# oled_control.net
KiCad netlist of a schematic drawn in Altium Designer
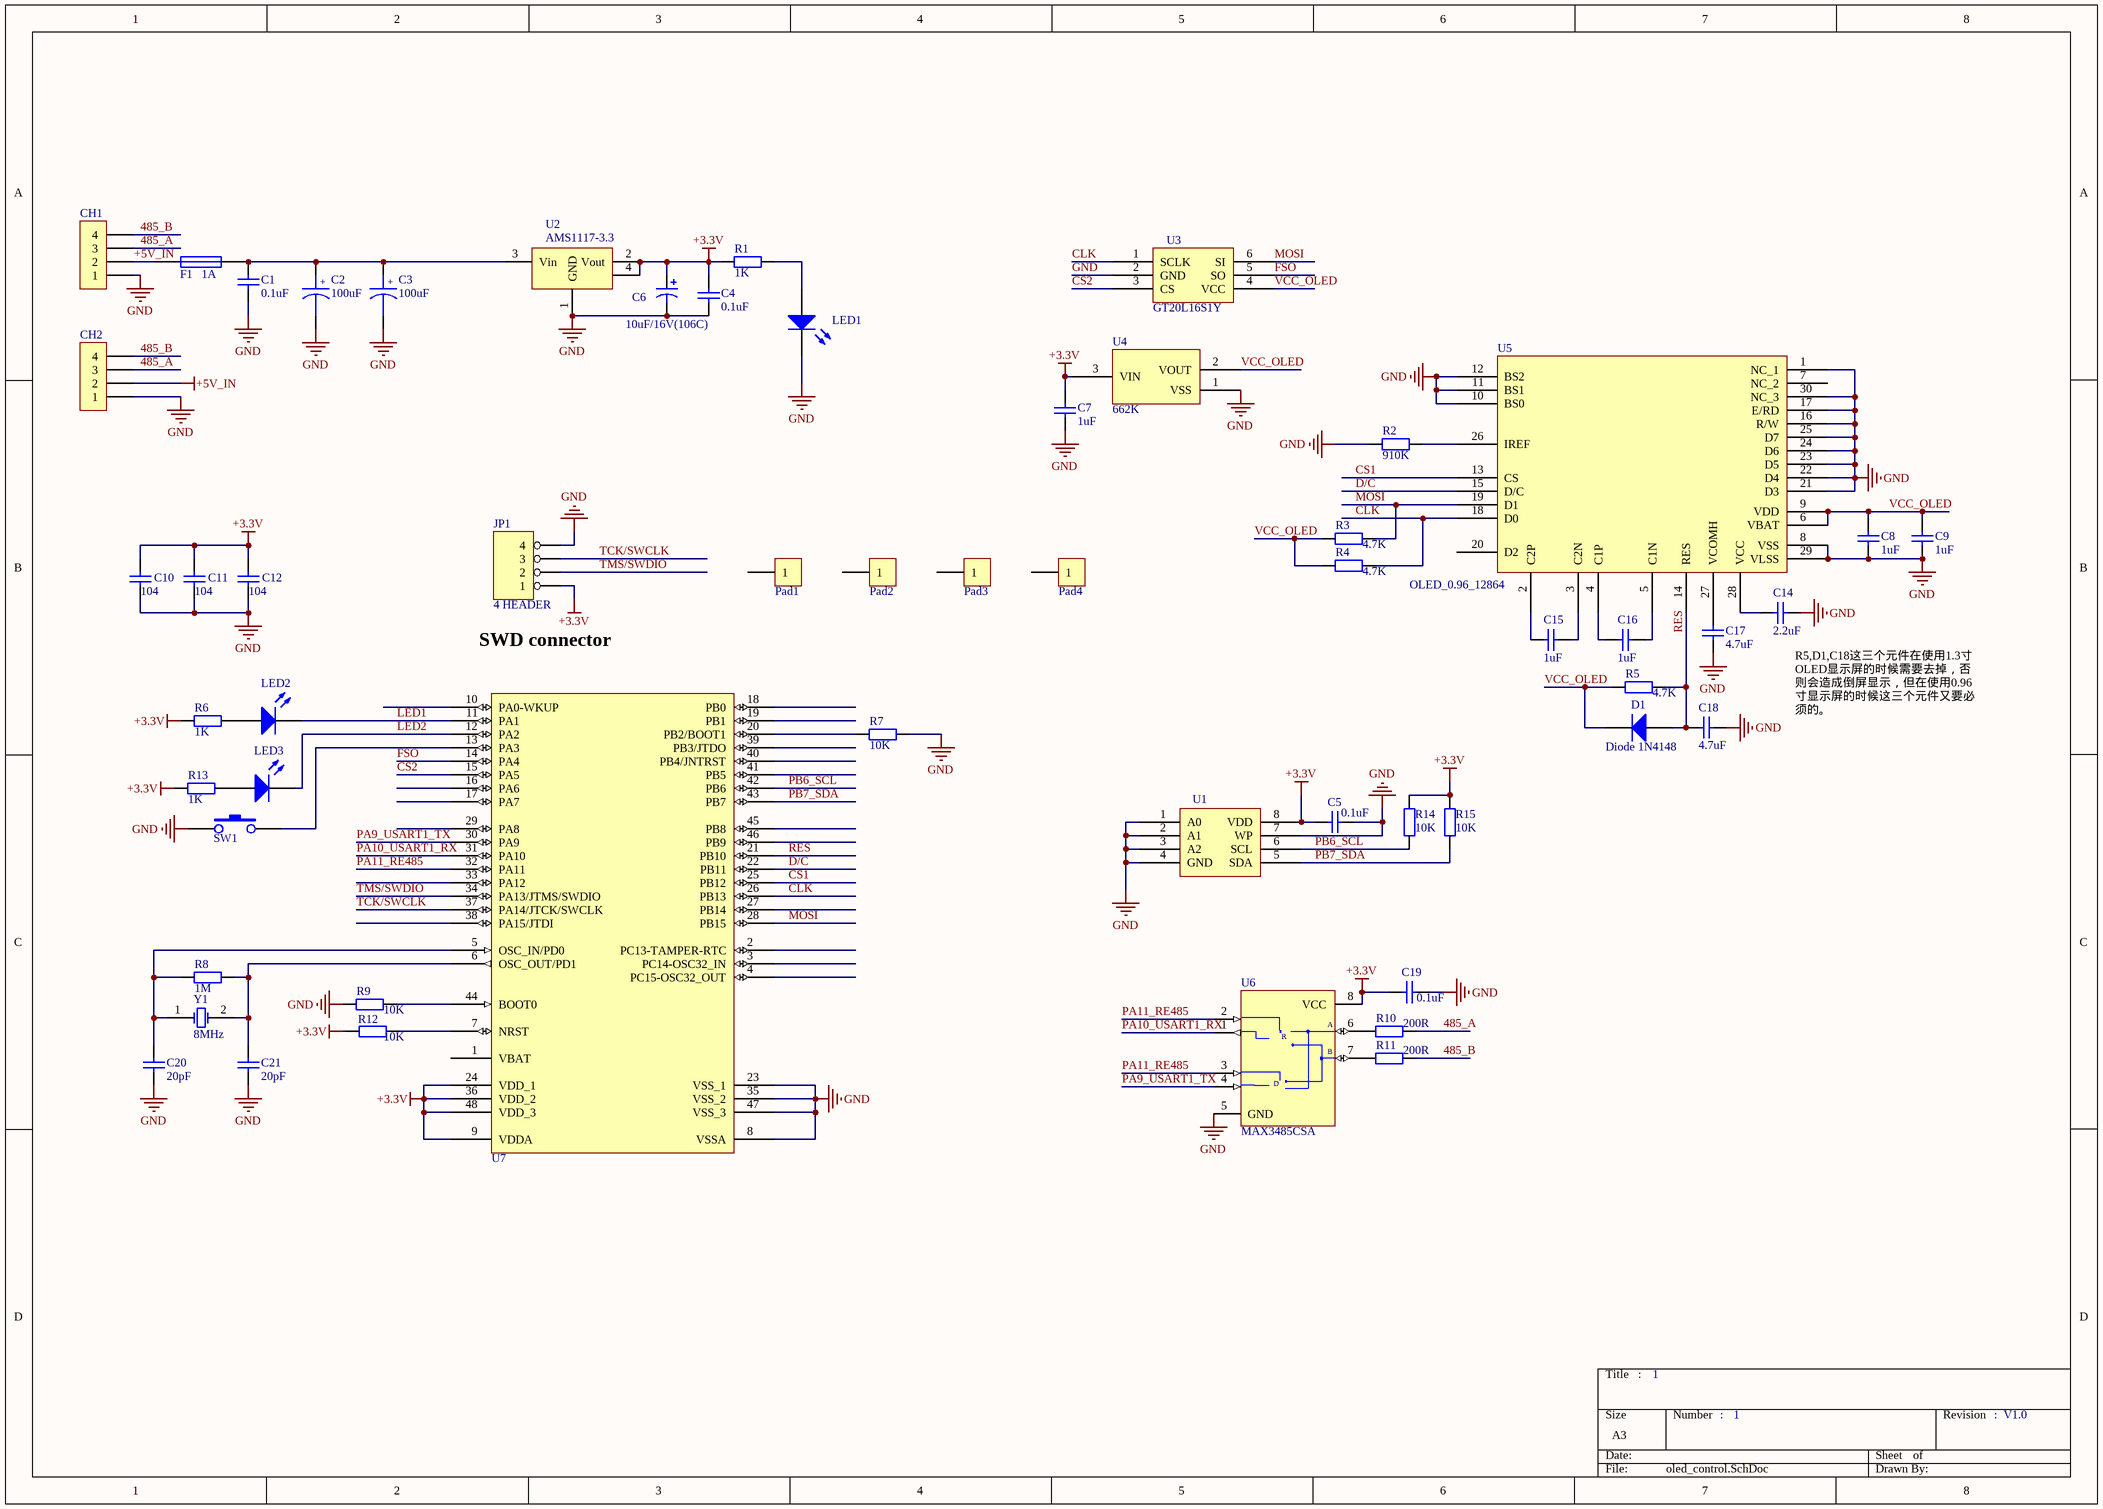
[diagram p0: oled_control.SchDoc]

(export (version "E")
  (design (tool "Eeschema 10.0.6"))
  (components
    (comp (ref "C1")
      (value "0.1uF")
      (footprint "0805")
      (description "Capacitor")
      (fields (field (name "Comment") "Cap") (field (name "PUBLISHER") "Altium Limited"))
      (libsource (lib "Miscellaneous Devices") (part "Cap"))
    )
    (comp (ref "C2")
      (value "C_2200uF")
      (footprint "B: 3528")
      (fields (field (name "ALTIUM_UNNAMED_1") "100uF"))
      (libsource (lib "myIntegrated_Library1") (part "C_2200uF"))
    )
    (comp (ref "C3")
      (value "C_2200uF")
      (footprint "B: 3528")
      (fields (field (name "ALTIUM_UNNAMED_1") "100uF"))
      (libsource (lib "myIntegrated_Library1") (part "C_2200uF"))
    )
    (comp (ref "C4")
      (value "0.1uF")
      (footprint "0805")
      (description "Capacitor")
      (fields (field (name "Comment") "Cap") (field (name "PUBLISHER") "Altium Limited"))
      (libsource (lib "Miscellaneous Devices") (part "Cap"))
    )
    (comp (ref "C5")
      (value "0.1uF")
      (footprint "0805")
      (description "Capacitor")
      (fields (field (name "Comment") "Cap") (field (name "PUBLISHER") "Altium Limited"))
      (libsource (lib "Miscellaneous Devices") (part "Cap"))
    )
    (comp (ref "C6")
      (value "10uF/16V(106C)")
      (footprint "CAP A-3216")
      (description "Polarized Capacitor (Surface Mount)")
      (fields (field (name "Comment") "Cap Pol3") (field (name "PUBLISHER") "Altium Limited"))
      (libsource (lib "Miscellaneous Devices") (part "Cap Pol3"))
    )
    (comp (ref "C7")
      (value "1uF")
      (footprint "0805")
      (description "Capacitor")
      (fields (field (name "Comment") "Cap") (field (name "PUBLISHER") "Altium Limited"))
      (libsource (lib "Miscellaneous Devices") (part "Cap"))
    )
    (comp (ref "C8")
      (value "1uF")
      (footprint "0805")
      (description "Capacitor")
      (fields (field (name "Comment") "Cap") (field (name "PUBLISHER") "Altium Limited"))
      (libsource (lib "Miscellaneous Devices") (part "Cap"))
    )
    (comp (ref "C9")
      (value "1uF")
      (footprint "0805")
      (description "Capacitor")
      (fields (field (name "Comment") "Cap") (field (name "PUBLISHER") "Altium Limited"))
      (libsource (lib "Miscellaneous Devices") (part "Cap"))
    )
    (comp (ref "C10")
      (value "104")
      (footprint "0805")
      (description "Capacitor")
      (fields (field (name "Comment") "Cap") (field (name "PUBLISHER") "Altium Limited"))
      (libsource (lib "Miscellaneous Devices") (part "Cap"))
    )
    (comp (ref "C11")
      (value "104")
      (footprint "0805")
      (description "Capacitor")
      (fields (field (name "Comment") "Cap") (field (name "PUBLISHER") "Altium Limited"))
      (libsource (lib "Miscellaneous Devices") (part "Cap"))
    )
    (comp (ref "C12")
      (value "104")
      (footprint "0805")
      (description "Capacitor")
      (fields (field (name "Comment") "Cap") (field (name "PUBLISHER") "Altium Limited"))
      (libsource (lib "Miscellaneous Devices") (part "Cap"))
    )
    (comp (ref "C14")
      (value "2.2uF")
      (footprint "0805")
      (description "Capacitor")
      (fields (field (name "Comment") "Cap") (field (name "PUBLISHER") "Altium Limited"))
      (libsource (lib "Miscellaneous Devices") (part "Cap"))
    )
    (comp (ref "C15")
      (value "1uF")
      (footprint "0805")
      (description "Capacitor")
      (fields (field (name "Comment") "Cap") (field (name "PUBLISHER") "Altium Limited"))
      (libsource (lib "Miscellaneous Devices") (part "Cap"))
    )
    (comp (ref "C16")
      (value "1uF")
      (footprint "0805")
      (description "Capacitor")
      (fields (field (name "Comment") "Cap") (field (name "PUBLISHER") "Altium Limited"))
      (libsource (lib "Miscellaneous Devices") (part "Cap"))
    )
    (comp (ref "C17")
      (value "4.7uF")
      (footprint "0805")
      (description "Capacitor")
      (fields (field (name "Comment") "Cap") (field (name "PUBLISHER") "Altium Limited"))
      (libsource (lib "Miscellaneous Devices") (part "Cap"))
    )
    (comp (ref "C18")
      (value "4.7uF")
      (footprint "0805")
      (description "Capacitor")
      (fields (field (name "Comment") "Cap") (field (name "PUBLISHER") "Altium Limited"))
      (libsource (lib "Miscellaneous Devices") (part "Cap"))
    )
    (comp (ref "C19")
      (value "0.1uF")
      (footprint "0805")
      (description "Capacitor")
      (fields (field (name "Comment") "Cap") (field (name "PUBLISHER") "Altium Limited"))
      (libsource (lib "Miscellaneous Devices") (part "Cap"))
    )
    (comp (ref "C20")
      (value "20pF")
      (footprint "0805")
      (description "Capacitor")
      (fields (field (name "Comment") "Cap") (field (name "PUBLISHER") "Altium Limited"))
      (libsource (lib "开发板元件库") (part "Cap"))
    )
    (comp (ref "C21")
      (value "20pF")
      (footprint "0805")
      (description "Capacitor")
      (fields (field (name "Comment") "Cap") (field (name "PUBLISHER") "Altium Limited"))
      (libsource (lib "开发板元件库") (part "Cap"))
    )
    (comp (ref "CH1")
      (value "HEADER1X4")
      (footprint "CON4_1.5")
      (libsource (lib "myIntegrated_Library1") (part "HEADER1X4"))
    )
    (comp (ref "CH2")
      (value "HEADER1X4")
      (footprint "CON4_1.5")
      (libsource (lib "myIntegrated_Library1") (part "HEADER1X4"))
    )
    (comp (ref "D1")
      (value "Diode 1N4148")
      (footprint "LL34")
      (description "High Conductance Fast Diode")
      (fields (field (name "PUBLISHER") "Altium Limited"))
      (libsource (lib "Miscellaneous Devices") (part "Diode 1N4148"))
    )
    (comp (ref "F1")
      (value "FUSE")
      (footprint "0805")
      (fields (field (name "ALTIUM_UNNAMED_1") "1A"))
      (libsource (lib "myIntegrated_Library1") (part "FUSE"))
    )
    (comp (ref "JP1")
      (value "4 HEADER")
      (footprint "CON4_1.5")
      (description "4 Pin Header")
      (libsource (lib "Miscellaneous Devices") (part "4 HEADER"))
    )
    (comp (ref "LED1")
      (value "~")
      (footprint "LED-0805")
      (description "Typical RED, GREEN, YELLOW, AMBER GaAs LED")
      (fields (field (name "PUBLISHER") "Altium Limited"))
      (libsource (lib "Miscellaneous Devices") (part "LED2"))
    )
    (comp (ref "LED2")
      (value "~")
      (footprint "LED-0805")
      (description "Typical RED, GREEN, YELLOW, AMBER GaAs LED")
      (fields (field (name "PUBLISHER") "Altium Limited"))
      (libsource (lib "Miscellaneous Devices") (part "LED2"))
    )
    (comp (ref "LED3")
      (value "~")
      (footprint "LED_5X5")
      (description "Typical RED, GREEN, YELLOW, AMBER GaAs LED")
      (fields (field (name "PUBLISHER") "Altium Limited"))
      (libsource (lib "Miscellaneous Devices") (part "LED2"))
    )
    (comp (ref "Pad1")
      (value "Pad")
      (footprint "pad35")
      (libsource (lib "myIntegrated_Library1") (part "Pad"))
    )
    (comp (ref "Pad2")
      (value "Pad")
      (footprint "pad35")
      (libsource (lib "myIntegrated_Library1") (part "Pad"))
    )
    (comp (ref "Pad3")
      (value "Pad")
      (footprint "pad35")
      (libsource (lib "myIntegrated_Library1") (part "Pad"))
    )
    (comp (ref "Pad4")
      (value "Pad")
      (footprint "pad35")
      (libsource (lib "myIntegrated_Library1") (part "Pad"))
    )
    (comp (ref "R1")
      (value "1K")
      (footprint "0805")
      (description "Resistor")
      (fields (field (name "Comment") "Res2") (field (name "PUBLISHER") "Altium Limited"))
      (libsource (lib "") (part "Res2_1"))
    )
    (comp (ref "R2")
      (value "910K")
      (footprint "0805")
      (description "Resistor")
      (fields (field (name "Comment") "Res2") (field (name "PUBLISHER") "Altium Limited"))
      (libsource (lib "") (part "Res2_1"))
    )
    (comp (ref "R3")
      (value "4.7K")
      (footprint "0805")
      (description "Resistor")
      (fields (field (name "Comment") "Res2") (field (name "PUBLISHER") "Altium Limited"))
      (libsource (lib "") (part "Res2_1"))
    )
    (comp (ref "R4")
      (value "4.7K")
      (footprint "0805")
      (description "Resistor")
      (fields (field (name "Comment") "Res2") (field (name "PUBLISHER") "Altium Limited"))
      (libsource (lib "") (part "Res2_1"))
    )
    (comp (ref "R5")
      (value "4.7K")
      (footprint "0805")
      (description "Resistor")
      (fields (field (name "Comment") "Res2") (field (name "PUBLISHER") "Altium Limited"))
      (libsource (lib "") (part "Res2_1"))
    )
    (comp (ref "R6")
      (value "1K")
      (footprint "0805")
      (description "Resistor")
      (fields (field (name "Comment") "Res2") (field (name "PUBLISHER") "Altium Limited"))
      (libsource (lib "") (part "Res2_1"))
    )
    (comp (ref "R7")
      (value "10K")
      (footprint "0805")
      (description "Resistor")
      (fields (field (name "Comment") "Res2") (field (name "PUBLISHER") "Altium Limited"))
      (libsource (lib "开发板元件库") (part "Res2"))
    )
    (comp (ref "R8")
      (value "1M")
      (footprint "0805")
      (description "Resistor")
      (fields (field (name "Comment") "Res2") (field (name "PUBLISHER") "Altium Limited"))
      (libsource (lib "开发板元件库") (part "Res2"))
    )
    (comp (ref "R9")
      (value "10K")
      (footprint "0805")
      (description "Resistor")
      (fields (field (name "Comment") "Res2") (field (name "PUBLISHER") "Altium Limited"))
      (libsource (lib "开发板元件库") (part "Res2"))
    )
    (comp (ref "R10")
      (value "200R")
      (footprint "0805")
      (description "Resistor")
      (fields (field (name "Comment") "Res2") (field (name "PUBLISHER") "Altium Limited"))
      (libsource (lib "") (part "Res2_2"))
    )
    (comp (ref "R11")
      (value "200R")
      (footprint "0805")
      (description "Resistor")
      (fields (field (name "Comment") "Res2") (field (name "PUBLISHER") "Altium Limited"))
      (libsource (lib "") (part "Res2_2"))
    )
    (comp (ref "R12")
      (value "10K")
      (footprint "0805")
      (description "Resistor")
      (fields (field (name "Comment") "Res2") (field (name "PUBLISHER") "Altium Limited"))
      (libsource (lib "开发板元件库") (part "Res2"))
    )
    (comp (ref "R13")
      (value "1K")
      (footprint "0805")
      (description "Resistor")
      (fields (field (name "Comment") "Res2") (field (name "PUBLISHER") "Altium Limited"))
      (libsource (lib "") (part "Res2_1"))
    )
    (comp (ref "R14")
      (value "10K")
      (footprint "C0805tan")
      (description "Resistor")
      (fields (field (name "Comment") "Res2") (field (name "PUBLISHER") "Altium Limited"))
      (libsource (lib "Miscellaneous Devices") (part "Res2"))
    )
    (comp (ref "R15")
      (value "10K")
      (footprint "C0805tan")
      (description "Resistor")
      (fields (field (name "Comment") "Res2") (field (name "PUBLISHER") "Altium Limited"))
      (libsource (lib "Miscellaneous Devices") (part "Res2"))
    )
    (comp (ref "SW1")
      (value "SW-KEY-2")
      (footprint "KEY_SOP4X4")
      (libsource (lib "myIntegrated_Library1") (part "SW-KEY-2"))
    )
    (comp (ref "U1")
      (value "AT24c02")
      (footprint "TSSOP8")
      (libsource (lib "myIntegrated_Library1") (part "TI24c02"))
    )
    (comp (ref "U2")
      (value "AMS1117-3.3")
      (footprint "SOT223")
      (libsource (lib "货架电子标签元件库") (part "AMS1117-5"))
    )
    (comp (ref "U3")
      (value "GT20L16S1Y")
      (footprint "SOT23-6")
      (libsource (lib "myIntegrated_Library1") (part "GT20L16S1Y"))
    )
    (comp (ref "U4")
      (value "662K")
      (footprint "SOT-23")
      (libsource (lib "myIntegrated_Library1") (part "662K"))
    )
    (comp (ref "U5")
      (value "OLED_0.96_12864")
      (footprint "OLED_1.30_12864")
      (libsource (lib "myIntegrated_Library1") (part "OLED_0.96_12864"))
    )
    (comp (ref "U6")
      (value "MAX3485CSA")
      (footprint "NS08-L")
      (libsource (lib "myIntegrated_Library1") (part "MAX485CSA"))
    )
    (comp (ref "U7")
      (value "STM32F103C8T6")
      (footprint "LQFP48")
      (libsource (lib "myIntegrated_Library1") (part "STM32F103C8T6"))
    )
    (comp (ref "Y1")
      (value "8MHz")
      (footprint "XTAL_US1")
      (description "Crystal Oscillator")
      (fields (field (name "PUBLISHER") "Altium Limited"))
      (libsource (lib "战舰STM32开发板底板封装库") (part "XTAL"))
    )
  )
  (nets
    (net (code "1") (name "+3.3V") (class "Default")
      (node (ref "C10") (pin "2") (pinfunction "2_2") (pintype "passive"))
      (node (ref "C11") (pin "2") (pinfunction "2_2") (pintype "passive"))
      (node (ref "C12") (pin "2") (pinfunction "2_2") (pintype "passive"))
      (node (ref "C19") (pin "1") (pinfunction "1_1") (pintype "passive"))
      (node (ref "C4") (pin "2") (pinfunction "2_2") (pintype "passive"))
      (node (ref "C5") (pin "2") (pinfunction "2_2") (pintype "passive"))
      (node (ref "C6") (pin "1") (pinfunction "1_1") (pintype "passive"))
      (node (ref "C7") (pin "1") (pinfunction "1_1") (pintype "passive"))
      (node (ref "JP1") (pin "1") (pinfunction "1_1") (pintype "passive"))
      (node (ref "R1") (pin "2") (pinfunction "2_2") (pintype "passive"))
      (node (ref "R12") (pin "1") (pinfunction "1_1") (pintype "passive"))
      (node (ref "R13") (pin "2") (pinfunction "2_2") (pintype "passive"))
      (node (ref "R14") (pin "2") (pinfunction "2_2") (pintype "passive"))
      (node (ref "R15") (pin "2") (pinfunction "2_2") (pintype "passive"))
      (node (ref "R6") (pin "2") (pinfunction "2_2") (pintype "passive"))
      (node (ref "U1") (pin "8") (pinfunction "VDD_8") (pintype "passive"))
      (node (ref "U2") (pin "2") (pinfunction "Vout_2") (pintype "passive"))
      (node (ref "U2") (pin "4") (pintype "passive"))
      (node (ref "U4") (pin "3") (pinfunction "VIN_3") (pintype "passive"))
      (node (ref "U6") (pin "8") (pinfunction "VCC_8") (pintype "power_in"))
      (node (ref "U7") (pin "24") (pinfunction "VDD_1_24") (pintype "power_in"))
      (node (ref "U7") (pin "36") (pinfunction "VDD_2_36") (pintype "power_in"))
      (node (ref "U7") (pin "48") (pinfunction "VDD_3_48") (pintype "power_in"))
      (node (ref "U7") (pin "9") (pinfunction "VDDA_9") (pintype "power_in"))
    )
    (net (code "2") (name "+5V_IN") (class "Default")
      (node (ref "CH1") (pin "2") (pinfunction "2_2") (pintype "passive"))
      (node (ref "CH2") (pin "2") (pinfunction "2_2") (pintype "passive"))
      (node (ref "F1") (pin "1") (pinfunction "1_1") (pintype "passive"))
    )
    (net (code "3") (name "/485_A") (class "Default")
      (node (ref "CH1") (pin "3") (pinfunction "3_3") (pintype "passive"))
      (node (ref "CH2") (pin "3") (pinfunction "3_3") (pintype "passive"))
      (node (ref "R10") (pin "2") (pinfunction "2_2") (pintype "passive"))
    )
    (net (code "4") (name "/485_B") (class "Default")
      (node (ref "CH1") (pin "4") (pinfunction "4_4") (pintype "passive"))
      (node (ref "CH2") (pin "4") (pinfunction "4_4") (pintype "passive"))
      (node (ref "R11") (pin "2") (pinfunction "2_2") (pintype "passive"))
    )
    (net (code "5") (name "/CLK") (class "Default")
      (node (ref "R4") (pin "1") (pinfunction "1_1") (pintype "passive"))
      (node (ref "U3") (pin "1") (pinfunction "SCLK_1") (pintype "passive"))
      (node (ref "U5") (pin "18") (pinfunction "D0_18") (pintype "passive"))
      (node (ref "U7") (pin "26") (pinfunction "PB13_26") (pintype "bidirectional"))
    )
    (net (code "6") (name "/CS1") (class "Default")
      (node (ref "U5") (pin "13") (pinfunction "CS_13") (pintype "passive"))
      (node (ref "U7") (pin "25") (pinfunction "PB12_25") (pintype "bidirectional"))
    )
    (net (code "7") (name "/CS2") (class "Default")
      (node (ref "U3") (pin "3") (pinfunction "CS_3") (pintype "passive"))
      (node (ref "U7") (pin "15") (pinfunction "PA5_15") (pintype "bidirectional"))
    )
    (net (code "8") (name "/D{slash}C") (class "Default")
      (node (ref "U5") (pin "15") (pinfunction "D/C_15") (pintype "passive"))
      (node (ref "U7") (pin "22") (pinfunction "PB11_22") (pintype "bidirectional"))
    )
    (net (code "9") (name "/FSO") (class "Default")
      (node (ref "U3") (pin "5") (pinfunction "SO_5") (pintype "passive"))
      (node (ref "U7") (pin "14") (pinfunction "PA4_14") (pintype "bidirectional"))
    )
    (net (code "10") (name "/LED1") (class "Default")
      (node (ref "LED2") (pin "2") (pinfunction "K_2") (pintype "passive"))
      (node (ref "U7") (pin "11") (pinfunction "PA1_11") (pintype "bidirectional"))
    )
    (net (code "11") (name "/LED2") (class "Default")
      (node (ref "LED3") (pin "2") (pinfunction "K_2") (pintype "passive"))
      (node (ref "U7") (pin "12") (pinfunction "PA2_12") (pintype "bidirectional"))
    )
    (net (code "12") (name "/MOSI") (class "Default")
      (node (ref "R3") (pin "1") (pinfunction "1_1") (pintype "passive"))
      (node (ref "U3") (pin "6") (pinfunction "SI_6") (pintype "passive"))
      (node (ref "U5") (pin "19") (pinfunction "D1_19") (pintype "passive"))
      (node (ref "U7") (pin "28") (pinfunction "PB15_28") (pintype "bidirectional"))
    )
    (net (code "13") (name "/PA9_USART1_TX") (class "Default")
      (node (ref "U6") (pin "4") (pinfunction "DI_4") (pintype "input"))
      (node (ref "U7") (pin "30") (pinfunction "PA9_30") (pintype "bidirectional"))
    )
    (net (code "14") (name "/PA10_USART1_RX") (class "Default")
      (node (ref "U6") (pin "1") (pinfunction "RO_1") (pintype "output"))
      (node (ref "U7") (pin "31") (pinfunction "PA10_31") (pintype "bidirectional"))
    )
    (net (code "15") (name "/PA11_RE485") (class "Default")
      (node (ref "U6") (pin "2") (pinfunction "~{RE}_2") (pintype "input"))
      (node (ref "U6") (pin "3") (pinfunction "DE_3") (pintype "input"))
      (node (ref "U7") (pin "32") (pinfunction "PA11_32") (pintype "bidirectional"))
    )
    (net (code "16") (name "/PB6_SCL") (class "Default")
      (node (ref "R14") (pin "1") (pinfunction "1_1") (pintype "passive"))
      (node (ref "U1") (pin "6") (pinfunction "SCL_6") (pintype "passive"))
      (node (ref "U7") (pin "42") (pinfunction "PB6_42") (pintype "bidirectional"))
    )
    (net (code "17") (name "/PB7_SDA") (class "Default")
      (node (ref "R15") (pin "1") (pinfunction "1_1") (pintype "passive"))
      (node (ref "U1") (pin "5") (pinfunction "SDA_5") (pintype "passive"))
      (node (ref "U7") (pin "43") (pinfunction "PB7_43") (pintype "bidirectional"))
    )
    (net (code "18") (name "/RES") (class "Default")
      (node (ref "C18") (pin "2") (pinfunction "2_2") (pintype "passive"))
      (node (ref "D1") (pin "1") (pinfunction "A_1") (pintype "passive"))
      (node (ref "R5") (pin "1") (pinfunction "1_1") (pintype "passive"))
      (node (ref "U5") (pin "14") (pinfunction "RES_14") (pintype "passive"))
      (node (ref "U7") (pin "21") (pinfunction "PB10_21") (pintype "bidirectional"))
    )
    (net (code "19") (name "/TCK{slash}SWCLK") (class "Default")
      (node (ref "JP1") (pin "3") (pinfunction "3_3") (pintype "passive"))
      (node (ref "U7") (pin "37") (pinfunction "PA14/JTCK/SWCLK_37") (pintype "bidirectional"))
    )
    (net (code "20") (name "/TMS{slash}SWDIO") (class "Default")
      (node (ref "JP1") (pin "2") (pinfunction "2_2") (pintype "passive"))
      (node (ref "U7") (pin "34") (pinfunction "PA13/JTMS/SWDIO_34") (pintype "bidirectional"))
    )
    (net (code "21") (name "/VCC_OLED") (class "Default")
      (node (ref "C8") (pin "1") (pinfunction "1_1") (pintype "passive"))
      (node (ref "C9") (pin "1") (pinfunction "1_1") (pintype "passive"))
      (node (ref "D1") (pin "2") (pinfunction "K_2") (pintype "passive"))
      (node (ref "R3") (pin "2") (pinfunction "2_2") (pintype "passive"))
      (node (ref "R4") (pin "2") (pinfunction "2_2") (pintype "passive"))
      (node (ref "R5") (pin "2") (pinfunction "2_2") (pintype "passive"))
      (node (ref "U3") (pin "4") (pinfunction "VCC_4") (pintype "passive"))
      (node (ref "U4") (pin "2") (pinfunction "VOUT_2") (pintype "passive"))
      (node (ref "U5") (pin "6") (pinfunction "VBAT_6") (pintype "passive"))
      (node (ref "U5") (pin "9") (pinfunction "VDD_9") (pintype "passive"))
    )
    (net (code "22") (name "GND") (class "Default")
      (node (ref "C1") (pin "1") (pinfunction "1_1") (pintype "passive"))
      (node (ref "C10") (pin "1") (pinfunction "1_1") (pintype "passive"))
      (node (ref "C11") (pin "1") (pinfunction "1_1") (pintype "passive"))
      (node (ref "C12") (pin "1") (pinfunction "1_1") (pintype "passive"))
      (node (ref "C14") (pin "1") (pinfunction "1_1") (pintype "passive"))
      (node (ref "C17") (pin "2") (pinfunction "2_2") (pintype "passive"))
      (node (ref "C18") (pin "1") (pinfunction "1_1") (pintype "passive"))
      (node (ref "C19") (pin "2") (pinfunction "2_2") (pintype "passive"))
      (node (ref "C2") (pin "2") (pinfunction "2_2") (pintype "passive"))
      (node (ref "C20") (pin "1") (pinfunction "1_1") (pintype "passive"))
      (node (ref "C21") (pin "1") (pinfunction "1_1") (pintype "passive"))
      (node (ref "C3") (pin "2") (pinfunction "2_2") (pintype "passive"))
      (node (ref "C4") (pin "1") (pinfunction "1_1") (pintype "passive"))
      (node (ref "C5") (pin "1") (pinfunction "1_1") (pintype "passive"))
      (node (ref "C6") (pin "2") (pinfunction "2_2") (pintype "passive"))
      (node (ref "C7") (pin "2") (pinfunction "2_2") (pintype "passive"))
      (node (ref "C8") (pin "2") (pinfunction "2_2") (pintype "passive"))
      (node (ref "C9") (pin "2") (pinfunction "2_2") (pintype "passive"))
      (node (ref "CH1") (pin "1") (pinfunction "1_1") (pintype "passive"))
      (node (ref "CH2") (pin "1") (pinfunction "1_1") (pintype "passive"))
      (node (ref "JP1") (pin "4") (pinfunction "4_4") (pintype "passive"))
      (node (ref "LED1") (pin "2") (pinfunction "K_2") (pintype "passive"))
      (node (ref "R2") (pin "2") (pinfunction "2_2") (pintype "passive"))
      (node (ref "R7") (pin "2") (pinfunction "2_2") (pintype "passive"))
      (node (ref "R9") (pin "1") (pinfunction "1_1") (pintype "passive"))
      (node (ref "SW1") (pin "1") (pinfunction "1_1") (pintype "passive"))
      (node (ref "U1") (pin "1") (pinfunction "A0_1") (pintype "passive"))
      (node (ref "U1") (pin "2") (pinfunction "A1_2") (pintype "passive"))
      (node (ref "U1") (pin "3") (pinfunction "A2_3") (pintype "passive"))
      (node (ref "U1") (pin "4") (pinfunction "GND_4") (pintype "passive"))
      (node (ref "U1") (pin "7") (pinfunction "WP_7") (pintype "passive"))
      (node (ref "U2") (pin "1") (pinfunction "GND_1") (pintype "passive"))
      (node (ref "U3") (pin "2") (pinfunction "GND_2") (pintype "passive"))
      (node (ref "U4") (pin "1") (pinfunction "VSS_1") (pintype "passive"))
      (node (ref "U5") (pin "1") (pinfunction "NC_1_1") (pintype "passive"))
      (node (ref "U5") (pin "10") (pinfunction "BS0_10") (pintype "passive"))
      (node (ref "U5") (pin "11") (pinfunction "BS1_11") (pintype "passive"))
      (node (ref "U5") (pin "12") (pinfunction "BS2_12") (pintype "passive"))
      (node (ref "U5") (pin "16") (pinfunction "R/W_16") (pintype "passive"))
      (node (ref "U5") (pin "17") (pinfunction "E/RD_17") (pintype "passive"))
      (node (ref "U5") (pin "21") (pinfunction "D3_21") (pintype "passive"))
      (node (ref "U5") (pin "22") (pinfunction "D4_22") (pintype "passive"))
      (node (ref "U5") (pin "23") (pinfunction "D5_23") (pintype "passive"))
      (node (ref "U5") (pin "24") (pinfunction "D6_24") (pintype "passive"))
      (node (ref "U5") (pin "25") (pinfunction "D7_25") (pintype "passive"))
      (node (ref "U5") (pin "29") (pinfunction "VLSS_29") (pintype "passive"))
      (node (ref "U5") (pin "30") (pinfunction "NC_3_30") (pintype "passive"))
      (node (ref "U5") (pin "8") (pinfunction "VSS_8") (pintype "passive"))
      (node (ref "U6") (pin "5") (pinfunction "GND_5") (pintype "power_in"))
      (node (ref "U7") (pin "23") (pinfunction "VSS_1_23") (pintype "power_in"))
      (node (ref "U7") (pin "35") (pinfunction "VSS_2_35") (pintype "power_in"))
      (node (ref "U7") (pin "47") (pinfunction "VSS_3_47") (pintype "power_in"))
      (node (ref "U7") (pin "8") (pinfunction "VSSA_8") (pintype "power_in"))
    )
    (net (code "23") (name "Net-(LED1-A)") (class "Default")
      (node (ref "LED1") (pin "1") (pinfunction "A_1") (pintype "passive"))
      (node (ref "R1") (pin "1") (pinfunction "1_1") (pintype "passive"))
    )
    (net (code "24") (name "Net-(LED2-A)") (class "Default")
      (node (ref "LED2") (pin "1") (pinfunction "A_1") (pintype "passive"))
      (node (ref "R6") (pin "1") (pinfunction "1_1") (pintype "passive"))
    )
    (net (code "25") (name "Net-(LED3-A)") (class "Default")
      (node (ref "LED3") (pin "1") (pinfunction "A_1") (pintype "passive"))
      (node (ref "R13") (pin "1") (pinfunction "1_1") (pintype "passive"))
    )
    (net (code "26") (name "Net-(U2-Vin)") (class "Default")
      (node (ref "C1") (pin "2") (pinfunction "2_2") (pintype "passive"))
      (node (ref "C2") (pin "1") (pinfunction "1_1") (pintype "passive"))
      (node (ref "C3") (pin "1") (pinfunction "1_1") (pintype "passive"))
      (node (ref "F1") (pin "2") (pinfunction "2_2") (pintype "passive"))
      (node (ref "U2") (pin "3") (pinfunction "Vin_3") (pintype "passive"))
    )
    (net (code "27") (name "Net-(U5-C1N)") (class "Default")
      (node (ref "C16") (pin "1") (pinfunction "1_1") (pintype "passive"))
      (node (ref "U5") (pin "5") (pinfunction "C1N_5") (pintype "passive"))
    )
    (net (code "28") (name "Net-(U5-C1P)") (class "Default")
      (node (ref "C16") (pin "2") (pinfunction "2_2") (pintype "passive"))
      (node (ref "U5") (pin "4") (pinfunction "C1P_4") (pintype "passive"))
    )
    (net (code "29") (name "Net-(U5-C2N)") (class "Default")
      (node (ref "C15") (pin "1") (pinfunction "1_1") (pintype "passive"))
      (node (ref "U5") (pin "3") (pinfunction "C2N_3") (pintype "passive"))
    )
    (net (code "30") (name "Net-(U5-C2P)") (class "Default")
      (node (ref "C15") (pin "2") (pinfunction "2_2") (pintype "passive"))
      (node (ref "U5") (pin "2") (pinfunction "C2P_2") (pintype "passive"))
    )
    (net (code "31") (name "Net-(U5-IREF)") (class "Default")
      (node (ref "R2") (pin "1") (pinfunction "1_1") (pintype "passive"))
      (node (ref "U5") (pin "26") (pinfunction "IREF_26") (pintype "passive"))
    )
    (net (code "32") (name "Net-(U5-VCC)") (class "Default")
      (node (ref "C14") (pin "2") (pinfunction "2_2") (pintype "passive"))
      (node (ref "U5") (pin "28") (pinfunction "VCC_28") (pintype "passive"))
    )
    (net (code "33") (name "Net-(U5-VCOMH)") (class "Default")
      (node (ref "C17") (pin "1") (pinfunction "1_1") (pintype "passive"))
      (node (ref "U5") (pin "27") (pinfunction "VCOMH_27") (pintype "passive"))
    )
    (net (code "34") (name "Net-(U6-A)") (class "Default")
      (node (ref "R10") (pin "1") (pinfunction "1_1") (pintype "passive"))
      (node (ref "U6") (pin "6") (pinfunction "A_6") (pintype "bidirectional"))
    )
    (net (code "35") (name "Net-(U6-B)") (class "Default")
      (node (ref "R11") (pin "1") (pinfunction "1_1") (pintype "passive"))
      (node (ref "U6") (pin "7") (pinfunction "B_7") (pintype "bidirectional"))
    )
    (net (code "36") (name "Net-(U7-BOOT0)") (class "Default")
      (node (ref "R9") (pin "2") (pinfunction "2_2") (pintype "passive"))
      (node (ref "U7") (pin "44") (pinfunction "BOOT0_44") (pintype "input"))
    )
    (net (code "37") (name "Net-(U7-NRST)") (class "Default")
      (node (ref "R12") (pin "2") (pinfunction "2_2") (pintype "passive"))
      (node (ref "U7") (pin "7") (pinfunction "NRST_7") (pintype "bidirectional"))
    )
    (net (code "38") (name "Net-(U7-OSC_IN{slash}PD0)") (class "Default")
      (node (ref "C20") (pin "2") (pinfunction "2_2") (pintype "passive"))
      (node (ref "R8") (pin "1") (pinfunction "1_1") (pintype "passive"))
      (node (ref "U7") (pin "5") (pinfunction "OSC_IN/PD0_5") (pintype "input"))
      (node (ref "Y1") (pin "1") (pinfunction "OSC1_1") (pintype "passive"))
    )
    (net (code "39") (name "Net-(U7-OSC_OUT{slash}PD1)") (class "Default")
      (node (ref "C21") (pin "2") (pinfunction "2_2") (pintype "passive"))
      (node (ref "R8") (pin "2") (pinfunction "2_2") (pintype "passive"))
      (node (ref "U7") (pin "6") (pinfunction "OSC_OUT/PD1_6") (pintype "output"))
      (node (ref "Y1") (pin "2") (pinfunction "OSC2_2") (pintype "passive"))
    )
    (net (code "40") (name "Net-(U7-PA3)") (class "Default")
      (node (ref "SW1") (pin "2") (pinfunction "2_2") (pintype "passive"))
      (node (ref "U7") (pin "13") (pinfunction "PA3_13") (pintype "bidirectional"))
    )
    (net (code "41") (name "Net-(U7-PB2{slash}BOOT1)") (class "Default")
      (node (ref "R7") (pin "1") (pinfunction "1_1") (pintype "passive"))
      (node (ref "U7") (pin "20") (pinfunction "PB2/BOOT1_20") (pintype "bidirectional"))
    )
    (net (code "42") (name "unconnected-(Pad1-Pad1)") (class "Default")
      (node (ref "Pad1") (pin "1") (pinfunction "1_1") (pintype "passive"))
    )
    (net (code "43") (name "unconnected-(Pad2-Pad1)") (class "Default")
      (node (ref "Pad2") (pin "1") (pinfunction "1_1") (pintype "passive"))
    )
    (net (code "44") (name "unconnected-(Pad3-Pad1)") (class "Default")
      (node (ref "Pad3") (pin "1") (pinfunction "1_1") (pintype "passive"))
    )
    (net (code "45") (name "unconnected-(Pad4-Pad1)") (class "Default")
      (node (ref "Pad4") (pin "1") (pinfunction "1_1") (pintype "passive"))
    )
    (net (code "46") (name "unconnected-(U5-D2-Pad20)") (class "Default")
      (node (ref "U5") (pin "20") (pinfunction "D2_20") (pintype "passive"))
    )
    (net (code "47") (name "unconnected-(U5-NC_2-Pad7)") (class "Default")
      (node (ref "U5") (pin "7") (pinfunction "NC_2_7") (pintype "passive"))
    )
    (net (code "48") (name "unconnected-(U7-PA0-WKUP-Pad10)") (class "Default")
      (node (ref "U7") (pin "10") (pinfunction "PA0-WKUP_10") (pintype "bidirectional"))
    )
    (net (code "49") (name "unconnected-(U7-PA6-Pad16)") (class "Default")
      (node (ref "U7") (pin "16") (pinfunction "PA6_16") (pintype "bidirectional"))
    )
    (net (code "50") (name "unconnected-(U7-PA7-Pad17)") (class "Default")
      (node (ref "U7") (pin "17") (pinfunction "PA7_17") (pintype "bidirectional"))
    )
    (net (code "51") (name "unconnected-(U7-PA8-Pad29)") (class "Default")
      (node (ref "U7") (pin "29") (pinfunction "PA8_29") (pintype "bidirectional"))
    )
    (net (code "52") (name "unconnected-(U7-PA12-Pad33)") (class "Default")
      (node (ref "U7") (pin "33") (pinfunction "PA12_33") (pintype "bidirectional"))
    )
    (net (code "53") (name "unconnected-(U7-PA15{slash}JTDI-Pad38)") (class "Default")
      (node (ref "U7") (pin "38") (pinfunction "PA15/JTDI_38") (pintype "bidirectional"))
    )
    (net (code "54") (name "unconnected-(U7-PB0-Pad18)") (class "Default")
      (node (ref "U7") (pin "18") (pinfunction "PB0_18") (pintype "bidirectional"))
    )
    (net (code "55") (name "unconnected-(U7-PB1-Pad19)") (class "Default")
      (node (ref "U7") (pin "19") (pinfunction "PB1_19") (pintype "bidirectional"))
    )
    (net (code "56") (name "unconnected-(U7-PB3{slash}JTDO-Pad39)") (class "Default")
      (node (ref "U7") (pin "39") (pinfunction "PB3/JTDO_39") (pintype "bidirectional"))
    )
    (net (code "57") (name "unconnected-(U7-PB4{slash}JNTRST-Pad40)") (class "Default")
      (node (ref "U7") (pin "40") (pinfunction "PB4/JNTRST_40") (pintype "bidirectional"))
    )
    (net (code "58") (name "unconnected-(U7-PB5-Pad41)") (class "Default")
      (node (ref "U7") (pin "41") (pinfunction "PB5_41") (pintype "bidirectional"))
    )
    (net (code "59") (name "unconnected-(U7-PB8-Pad45)") (class "Default")
      (node (ref "U7") (pin "45") (pinfunction "PB8_45") (pintype "bidirectional"))
    )
    (net (code "60") (name "unconnected-(U7-PB9-Pad46)") (class "Default")
      (node (ref "U7") (pin "46") (pinfunction "PB9_46") (pintype "bidirectional"))
    )
    (net (code "61") (name "unconnected-(U7-PB14-Pad27)") (class "Default")
      (node (ref "U7") (pin "27") (pinfunction "PB14_27") (pintype "bidirectional"))
    )
    (net (code "62") (name "unconnected-(U7-PC13-TAMPER-RTC-Pad2)") (class "Default")
      (node (ref "U7") (pin "2") (pinfunction "PC13-TAMPER-RTC_2") (pintype "bidirectional"))
    )
    (net (code "63") (name "unconnected-(U7-PC14-OSC32_IN-Pad3)") (class "Default")
      (node (ref "U7") (pin "3") (pinfunction "PC14-OSC32_IN_3") (pintype "bidirectional"))
    )
    (net (code "64") (name "unconnected-(U7-PC15-OSC32_OUT-Pad4)") (class "Default")
      (node (ref "U7") (pin "4") (pinfunction "PC15-OSC32_OUT_4") (pintype "bidirectional"))
    )
    (net (code "65") (name "unconnected-(U7-VBAT-Pad1)") (class "Default")
      (node (ref "U7") (pin "1") (pinfunction "VBAT_1") (pintype "power_in"))
    )
  )
)
